# AltiumDesigner_-_Sheet_3.net
KiCad netlist of a schematic drawn in Altium Designer
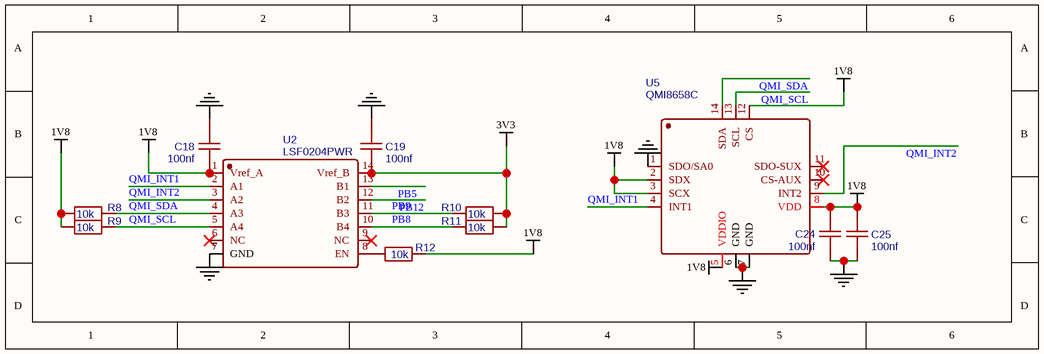
[diagram p0: AltiumDesigner - Sheet_3.schdoc]

(export (version "E")
  (design (tool "Eeschema 10.0.6"))
  (components
    (comp (ref "C18")
      (value "100nf")
      (fields (field (name "CONTRIBUTOR") "LCEDA_Lib"))
      (libsource (lib "") (part "root_1_100nf__1"))
    )
    (comp (ref "C19")
      (value "100nf")
      (fields (field (name "CONTRIBUTOR") "LCEDA_Lib"))
      (libsource (lib "altium-import") (part "root_1_100nf_"))
    )
    (comp (ref "C24")
      (value "100nf")
      (fields (field (name "CONTRIBUTOR") "LCEDA_Lib"))
      (libsource (lib "altium-import") (part "root_3_100nf_"))
    )
    (comp (ref "C25")
      (value "100nf")
      (fields (field (name "CONTRIBUTOR") "LCEDA_Lib"))
      (libsource (lib "altium-import") (part "root_1_100nf_"))
    )
    (comp (ref "R8")
      (value "10k")
      (fields (field (name "CONTRIBUTOR") "LCEDA_Lib"))
      (libsource (lib "altium-import") (part "root_0_10k_"))
    )
    (comp (ref "R9")
      (value "10k")
      (fields (field (name "CONTRIBUTOR") "LCEDA_Lib"))
      (libsource (lib "altium-import") (part "root_0_10k_"))
    )
    (comp (ref "R10")
      (value "10k")
      (fields (field (name "CONTRIBUTOR") "LCEDA_Lib"))
      (libsource (lib "altium-import") (part "root_0_10k_"))
    )
    (comp (ref "R11")
      (value "10k")
      (fields (field (name "CONTRIBUTOR") "LCEDA_Lib"))
      (libsource (lib "altium-import") (part "root_0_10k_"))
    )
    (comp (ref "R12")
      (value "10k")
      (fields (field (name "CONTRIBUTOR") "LCEDA_Lib"))
      (libsource (lib "") (part "root_0_10k__1"))
    )
    (comp (ref "U2")
      (value "LSF0204PWR")
      (fields (field (name "BOM_SUPPLIER PART") "C202288") (field (name "CONTRIBUTOR") "LCSC"))
      (libsource (lib "altium-import") (part "root_0_LSF0204PWR_"))
    )
    (comp (ref "U5")
      (value "QMI8658C")
      (fields (field (name "BOM_SUPPLIER PART") "C2842151") (field (name "CONTRIBUTOR") "LCSC"))
      (libsource (lib "altium-import") (part "root_0_QMI8658C_"))
    )
  )
  (nets
    (net (code "1") (name "/PB5") (class "Default")
      (node (ref "U2") (pin "13") (pinfunction "B1_13") (pintype "passive"))
    )
    (net (code "2") (name "/PB8") (class "Default")
      (node (ref "R11") (pin "1") (pinfunction "1_1") (pintype "passive"))
      (node (ref "U2") (pin "10") (pinfunction "B4_10") (pintype "passive"))
    )
    (net (code "3") (name "/PB9") (class "Default")
      (node (ref "R10") (pin "1") (pinfunction "1_1") (pintype "passive"))
      (node (ref "U2") (pin "11") (pinfunction "B3_11") (pintype "passive"))
    )
    (net (code "4") (name "/PB12") (class "Default")
      (node (ref "U2") (pin "12") (pinfunction "B2_12") (pintype "passive"))
    )
    (net (code "5") (name "/QMI_INT1") (class "Default")
      (node (ref "U2") (pin "2") (pinfunction "A1_2") (pintype "passive"))
      (node (ref "U5") (pin "4") (pinfunction "INT1_4") (pintype "passive"))
    )
    (net (code "6") (name "/QMI_INT2") (class "Default")
      (node (ref "U2") (pin "3") (pinfunction "A2_3") (pintype "passive"))
      (node (ref "U5") (pin "9") (pinfunction "INT2_9") (pintype "passive"))
    )
    (net (code "7") (name "/QMI_SCL") (class "Default")
      (node (ref "R9") (pin "2") (pinfunction "2_2") (pintype "passive"))
      (node (ref "U2") (pin "5") (pinfunction "A4_5") (pintype "passive"))
      (node (ref "U5") (pin "13") (pinfunction "SCL_13") (pintype "passive"))
    )
    (net (code "8") (name "/QMI_SDA") (class "Default")
      (node (ref "R8") (pin "2") (pinfunction "2_2") (pintype "passive"))
      (node (ref "U2") (pin "4") (pinfunction "A3_4") (pintype "passive"))
      (node (ref "U5") (pin "14") (pinfunction "SDA_14") (pintype "passive"))
    )
    (net (code "9") (name "1V8") (class "Default")
      (node (ref "C18") (pin "1") (pinfunction "1_1") (pintype "passive"))
      (node (ref "C24") (pin "1") (pinfunction "1_1") (pintype "passive"))
      (node (ref "C25") (pin "2") (pinfunction "2_2") (pintype "passive"))
      (node (ref "R12") (pin "1") (pinfunction "1_1") (pintype "passive"))
      (node (ref "R8") (pin "1") (pinfunction "1_1") (pintype "passive"))
      (node (ref "R9") (pin "1") (pinfunction "1_1") (pintype "passive"))
      (node (ref "U2") (pin "1") (pinfunction "Vref_A_1") (pintype "passive"))
      (node (ref "U5") (pin "12") (pinfunction "CS_12") (pintype "passive"))
      (node (ref "U5") (pin "2") (pinfunction "SDX_2") (pintype "passive"))
      (node (ref "U5") (pin "3") (pinfunction "SCX_3") (pintype "passive"))
      (node (ref "U5") (pin "5") (pinfunction "VDDIO_5") (pintype "passive"))
      (node (ref "U5") (pin "8") (pinfunction "VDD_8") (pintype "passive"))
    )
    (net (code "10") (name "3V3") (class "Default")
      (node (ref "C19") (pin "1") (pinfunction "1_1") (pintype "passive"))
      (node (ref "R10") (pin "2") (pinfunction "2_2") (pintype "passive"))
      (node (ref "R11") (pin "2") (pinfunction "2_2") (pintype "passive"))
      (node (ref "U2") (pin "14") (pinfunction "Vref_B_14") (pintype "passive"))
    )
    (net (code "11") (name "GND") (class "Default")
      (node (ref "C18") (pin "2") (pinfunction "2_2") (pintype "passive"))
      (node (ref "C19") (pin "2") (pinfunction "2_2") (pintype "passive"))
      (node (ref "C24") (pin "2") (pinfunction "2_2") (pintype "passive"))
      (node (ref "C25") (pin "1") (pinfunction "1_1") (pintype "passive"))
      (node (ref "U2") (pin "7") (pinfunction "GND_7") (pintype "passive"))
      (node (ref "U5") (pin "1") (pinfunction "SDO/SA0_1") (pintype "passive"))
      (node (ref "U5") (pin "6") (pinfunction "GND_6") (pintype "passive"))
      (node (ref "U5") (pin "7") (pinfunction "GND_7") (pintype "passive"))
    )
    (net (code "12") (name "Net-(U2-EN)") (class "Default")
      (node (ref "R12") (pin "2") (pinfunction "2_2") (pintype "passive"))
      (node (ref "U2") (pin "8") (pinfunction "EN_8") (pintype "passive"))
    )
    (net (code "13") (name "unconnected-(U2-NC-Pad6)") (class "Default")
      (node (ref "U2") (pin "6") (pinfunction "NC_6") (pintype "passive+no_connect"))
    )
    (net (code "14") (name "unconnected-(U2-NC-Pad9)") (class "Default")
      (node (ref "U2") (pin "9") (pinfunction "NC_9") (pintype "passive+no_connect"))
    )
    (net (code "15") (name "unconnected-(U5-CS-AUX-Pad10)") (class "Default")
      (node (ref "U5") (pin "10") (pinfunction "CS-AUX_10") (pintype "passive+no_connect"))
    )
    (net (code "16") (name "unconnected-(U5-SDO-SUX-Pad11)") (class "Default")
      (node (ref "U5") (pin "11") (pinfunction "SDO-SUX_11") (pintype "passive+no_connect"))
    )
  )
)
